# BTModule.net
KiCad netlist of a schematic drawn in EAGLE
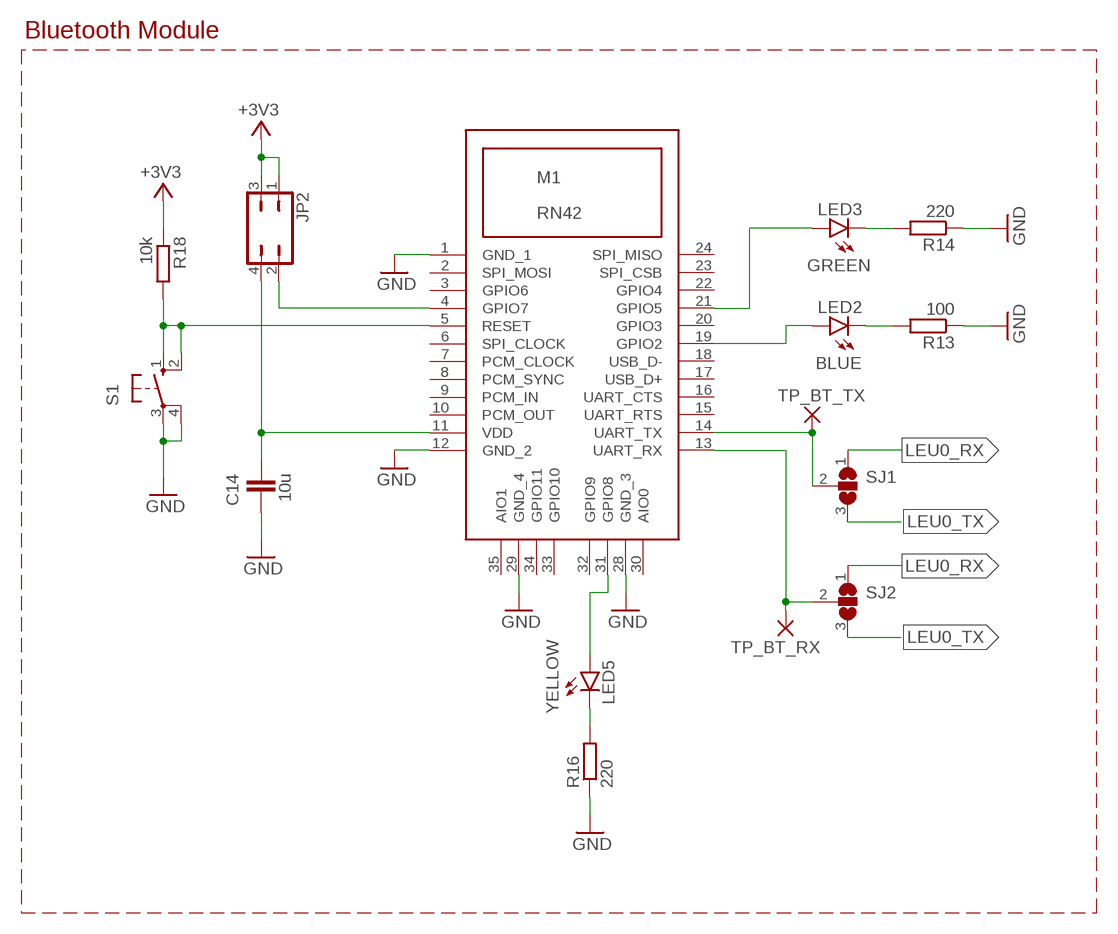
[diagram p0: schematic, sheet 1]

(export (version "E")
  (design (tool "Eeschema 10.0.6"))
  (components
    (comp (ref "C14")
      (value "10u")
      (footprint "eagle-import:C0805K")
      (libsource (lib "eagle-import") (part "C-EUC0805K"))
    )
    (comp (ref "JP2")
      (value "JP2Q")
      (footprint "eagle-import:JP2Q")
      (libsource (lib "eagle-import") (part "JP2Q"))
    )
    (comp (ref "LED2")
      (value "BLUE")
      (footprint "eagle-import:CHIP-LED0805")
      (fields (field (name "SPICEPREFIX") "L"))
      (libsource (lib "eagle-import") (part "LEDCHIP-LED0805"))
    )
    (comp (ref "LED3")
      (value "GREEN")
      (footprint "eagle-import:CHIP-LED0805")
      (fields (field (name "SPICEPREFIX") "L"))
      (libsource (lib "eagle-import") (part "LEDCHIP-LED0805"))
    )
    (comp (ref "LED5")
      (value "YELLOW")
      (footprint "eagle-import:CHIP-LED0805")
      (fields (field (name "SPICEPREFIX") "L"))
      (libsource (lib "eagle-import") (part "LEDCHIP-LED0805"))
    )
    (comp (ref "M1")
      (value "RN42_BLUETOOTH")
      (footprint "eagle-import:RN42_BLUETOOTH")
      (libsource (lib "eagle-import") (part "RN42_BLUETOOTH"))
    )
    (comp (ref "R13")
      (value "100")
      (footprint "eagle-import:R0805")
      (libsource (lib "eagle-import") (part "R-EU_R0805"))
    )
    (comp (ref "R14")
      (value "220")
      (footprint "eagle-import:R0805")
      (libsource (lib "eagle-import") (part "R-EU_R0805"))
    )
    (comp (ref "R16")
      (value "220")
      (footprint "eagle-import:R0805")
      (libsource (lib "eagle-import") (part "R-EU_R0805"))
    )
    (comp (ref "R18")
      (value "10k")
      (footprint "eagle-import:R0805")
      (libsource (lib "eagle-import") (part "R-EU_R0805"))
    )
    (comp (ref "S1")
      (value "10-XX")
      (footprint "eagle-import:B3F-10XX")
      (fields (field (name "MPN") "B3F-1000"))
      (libsource (lib "eagle-import") (part "10-XX"))
    )
    (comp (ref "SJ1")
      (value "SJ2W")
      (footprint "eagle-import:SJ_2")
      (libsource (lib "eagle-import") (part "SJ2W"))
    )
    (comp (ref "SJ2")
      (value "SJ2W")
      (footprint "eagle-import:SJ_2")
      (libsource (lib "eagle-import") (part "SJ2W"))
    )
    (comp (ref "TP_BT_RX")
      (value "TESTPOINT")
      (footprint "eagle-import:3,2_1,6")
      (libsource (lib "eagle-import") (part "TESTPOINT"))
    )
    (comp (ref "TP_BT_TX")
      (value "TESTPOINT")
      (footprint "eagle-import:3,2_1,6")
      (libsource (lib "eagle-import") (part "TESTPOINT"))
    )
  )
  (nets
    (net (code "1") (name "+3V3") (class "Default")
      (node (ref "JP2") (pin "1") (pinfunction "1_1") (pintype "passive"))
      (node (ref "JP2") (pin "3") (pinfunction "3_3") (pintype "passive"))
      (node (ref "R18") (pin "1") (pinfunction "1_1") (pintype "passive"))
    )
    (net (code "2") (name "GND") (class "Default")
      (node (ref "C14") (pin "1") (pinfunction "1_1") (pintype "passive"))
      (node (ref "M1") (pin "1") (pinfunction "GND_1_1") (pintype "bidirectional"))
      (node (ref "M1") (pin "12") (pinfunction "GND_2_12") (pintype "bidirectional"))
      (node (ref "M1") (pin "28") (pinfunction "GND_3_28") (pintype "bidirectional"))
      (node (ref "M1") (pin "29") (pinfunction "GND_4_29") (pintype "bidirectional"))
      (node (ref "R13") (pin "1") (pinfunction "1_1") (pintype "passive"))
      (node (ref "R14") (pin "1") (pinfunction "1_1") (pintype "passive"))
      (node (ref "R16") (pin "1") (pinfunction "1_1") (pintype "passive"))
      (node (ref "S1") (pin "3") (pinfunction "P_3") (pintype "passive"))
      (node (ref "S1") (pin "4") (pinfunction "P1_4") (pintype "passive"))
    )
    (net (code "3") (name "LEU0_RX") (class "Default")
      (node (ref "SJ1") (pin "1") (pinfunction "1_1") (pintype "passive"))
      (node (ref "SJ2") (pin "1") (pinfunction "1_1") (pintype "passive"))
    )
    (net (code "4") (name "LEU0_TX") (class "Default")
      (node (ref "SJ1") (pin "3") (pinfunction "3_3") (pintype "passive"))
      (node (ref "SJ2") (pin "3") (pinfunction "3_3") (pintype "passive"))
    )
    (net (code "5") (name "Net-(LED2-PadC)") (class "Default")
      (node (ref "LED2") (pin "C") (pinfunction "C_C") (pintype "passive"))
      (node (ref "R13") (pin "2") (pinfunction "2_2") (pintype "passive"))
    )
    (net (code "6") (name "Net-(LED3-PadC)") (class "Default")
      (node (ref "LED3") (pin "C") (pinfunction "C_C") (pintype "passive"))
      (node (ref "R14") (pin "2") (pinfunction "2_2") (pintype "passive"))
    )
    (net (code "7") (name "Net-(LED5-PadC)") (class "Default")
      (node (ref "LED5") (pin "C") (pinfunction "C_C") (pintype "passive"))
      (node (ref "R16") (pin "2") (pinfunction "2_2") (pintype "passive"))
    )
    (net (code "8") (name "Net-(M1-GPIO2)") (class "Default")
      (node (ref "LED2") (pin "A") (pinfunction "A_A") (pintype "passive"))
      (node (ref "M1") (pin "19") (pinfunction "GPIO2_19") (pintype "bidirectional"))
    )
    (net (code "9") (name "Net-(M1-GPIO5)") (class "Default")
      (node (ref "LED3") (pin "A") (pinfunction "A_A") (pintype "passive"))
      (node (ref "M1") (pin "21") (pinfunction "GPIO5_21") (pintype "bidirectional"))
    )
    (net (code "10") (name "Net-(M1-GPIO7)") (class "Default")
      (node (ref "JP2") (pin "2") (pinfunction "2_2") (pintype "passive"))
      (node (ref "M1") (pin "4") (pinfunction "GPIO7_4") (pintype "bidirectional"))
    )
    (net (code "11") (name "Net-(M1-GPIO8)") (class "Default")
      (node (ref "LED5") (pin "A") (pinfunction "A_A") (pintype "passive"))
      (node (ref "M1") (pin "31") (pinfunction "GPIO8_31") (pintype "bidirectional"))
    )
    (net (code "12") (name "Net-(M1-RESET)") (class "Default")
      (node (ref "M1") (pin "5") (pinfunction "RESET_5") (pintype "bidirectional"))
      (node (ref "R18") (pin "2") (pinfunction "2_2") (pintype "passive"))
      (node (ref "S1") (pin "1") (pinfunction "S_1") (pintype "passive"))
      (node (ref "S1") (pin "2") (pinfunction "S1_2") (pintype "passive"))
    )
    (net (code "13") (name "Net-(M1-UART_RX)") (class "Default")
      (node (ref "M1") (pin "13") (pinfunction "UART_RX_13") (pintype "bidirectional"))
      (node (ref "SJ2") (pin "2") (pinfunction "2_2") (pintype "passive"))
      (node (ref "TP_BT_RX") (pin "1") (pinfunction "P_1") (pintype "passive"))
    )
    (net (code "14") (name "Net-(M1-UART_TX)") (class "Default")
      (node (ref "M1") (pin "14") (pinfunction "UART_TX_14") (pintype "bidirectional"))
      (node (ref "SJ1") (pin "2") (pinfunction "2_2") (pintype "passive"))
      (node (ref "TP_BT_TX") (pin "1") (pinfunction "P_1") (pintype "passive"))
    )
    (net (code "15") (name "Net-(M1-VDD)") (class "Default")
      (node (ref "C14") (pin "2") (pinfunction "2_2") (pintype "passive"))
      (node (ref "JP2") (pin "4") (pinfunction "4_4") (pintype "passive"))
      (node (ref "M1") (pin "11") (pinfunction "VDD_11") (pintype "bidirectional"))
    )
    (net (code "16") (name "unconnected-(M1-AIO0-Pad30)") (class "Default")
      (node (ref "M1") (pin "30") (pinfunction "AIO0_30") (pintype "bidirectional"))
    )
    (net (code "17") (name "unconnected-(M1-AIO1-Pad35)") (class "Default")
      (node (ref "M1") (pin "35") (pinfunction "AIO1_35") (pintype "bidirectional"))
    )
    (net (code "18") (name "unconnected-(M1-GPIO3-Pad20)") (class "Default")
      (node (ref "M1") (pin "20") (pinfunction "GPIO3_20") (pintype "bidirectional"))
    )
    (net (code "19") (name "unconnected-(M1-GPIO4-Pad22)") (class "Default")
      (node (ref "M1") (pin "22") (pinfunction "GPIO4_22") (pintype "bidirectional"))
    )
    (net (code "20") (name "unconnected-(M1-GPIO6-Pad3)") (class "Default")
      (node (ref "M1") (pin "3") (pinfunction "GPIO6_3") (pintype "bidirectional"))
    )
    (net (code "21") (name "unconnected-(M1-GPIO9-Pad32)") (class "Default")
      (node (ref "M1") (pin "32") (pinfunction "GPIO9_32") (pintype "bidirectional"))
    )
    (net (code "22") (name "unconnected-(M1-GPIO10-Pad33)") (class "Default")
      (node (ref "M1") (pin "33") (pinfunction "GPIO10_33") (pintype "bidirectional"))
    )
    (net (code "23") (name "unconnected-(M1-GPIO11-Pad34)") (class "Default")
      (node (ref "M1") (pin "34") (pinfunction "GPIO11_34") (pintype "bidirectional"))
    )
    (net (code "24") (name "unconnected-(M1-PCM_CLOCK-Pad7)") (class "Default")
      (node (ref "M1") (pin "7") (pinfunction "PCM_CLOCK_7") (pintype "bidirectional"))
    )
    (net (code "25") (name "unconnected-(M1-PCM_IN-Pad9)") (class "Default")
      (node (ref "M1") (pin "9") (pinfunction "PCM_IN_9") (pintype "bidirectional"))
    )
    (net (code "26") (name "unconnected-(M1-PCM_OUT-Pad10)") (class "Default")
      (node (ref "M1") (pin "10") (pinfunction "PCM_OUT_10") (pintype "bidirectional"))
    )
    (net (code "27") (name "unconnected-(M1-PCM_SYNC-Pad8)") (class "Default")
      (node (ref "M1") (pin "8") (pinfunction "PCM_SYNC_8") (pintype "bidirectional"))
    )
    (net (code "28") (name "unconnected-(M1-SPI_CLOCK-Pad6)") (class "Default")
      (node (ref "M1") (pin "6") (pinfunction "SPI_CLOCK_6") (pintype "bidirectional"))
    )
    (net (code "29") (name "unconnected-(M1-SPI_CSB-Pad23)") (class "Default")
      (node (ref "M1") (pin "23") (pinfunction "SPI_CSB_23") (pintype "bidirectional"))
    )
    (net (code "30") (name "unconnected-(M1-SPI_MISO-Pad24)") (class "Default")
      (node (ref "M1") (pin "24") (pinfunction "SPI_MISO_24") (pintype "bidirectional"))
    )
    (net (code "31") (name "unconnected-(M1-SPI_MOSI-Pad2)") (class "Default")
      (node (ref "M1") (pin "2") (pinfunction "SPI_MOSI_2") (pintype "bidirectional"))
    )
    (net (code "32") (name "unconnected-(M1-UART_CTS-Pad16)") (class "Default")
      (node (ref "M1") (pin "16") (pinfunction "UART_CTS_16") (pintype "bidirectional"))
    )
    (net (code "33") (name "unconnected-(M1-UART_RTS-Pad15)") (class "Default")
      (node (ref "M1") (pin "15") (pinfunction "UART_RTS_15") (pintype "bidirectional"))
    )
    (net (code "34") (name "unconnected-(M1-USB_D+-Pad17)") (class "Default")
      (node (ref "M1") (pin "17") (pinfunction "USB_D+_17") (pintype "bidirectional"))
    )
    (net (code "35") (name "unconnected-(M1-USB_D--Pad18)") (class "Default")
      (node (ref "M1") (pin "18") (pinfunction "USB_D-_18") (pintype "bidirectional"))
    )
  )
)
